# Dispenser.net
KiCad netlist of a schematic drawn in Altium Designer
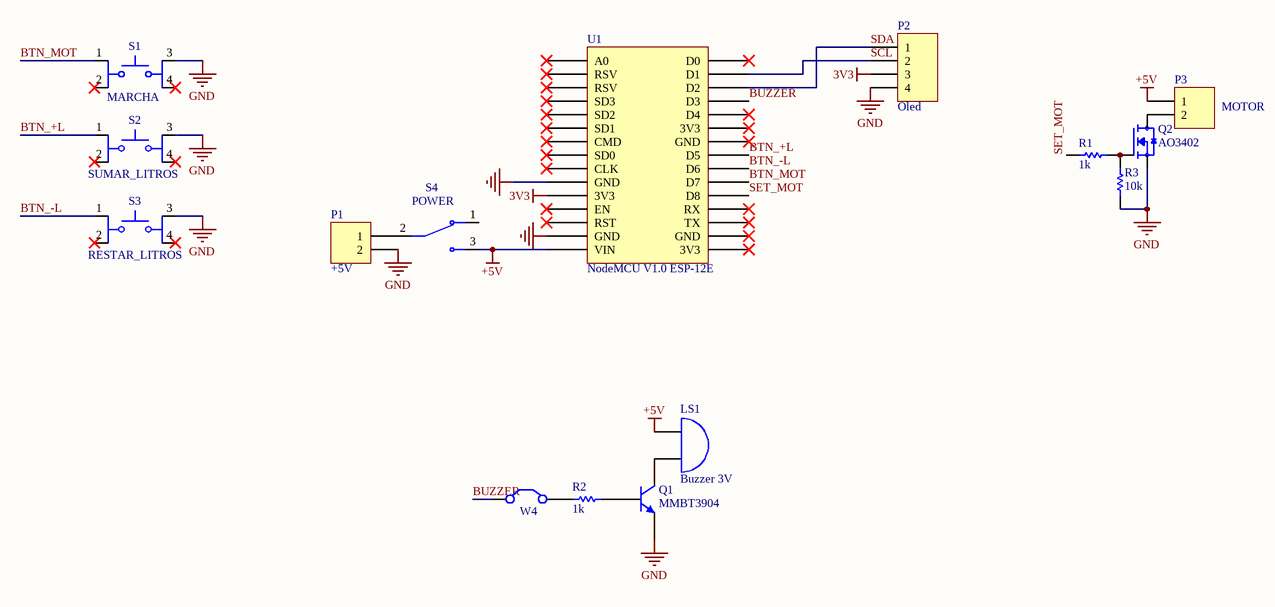
[diagram p0: Dispenser.SchDoc]

(export (version "E")
  (design (tool "Eeschema 10.0.6"))
  (components
    (comp (ref "LS1")
      (value "Buzzer 3V")
      (footprint "BUZZER")
      (description "Electrical Bell")
      (fields (field (name "PUBLISHER") "Altium Limited"))
      (libsource (lib "Miscellaneous Devices") (part "Bell"))
    )
    (comp (ref "P1")
      (value "+5V")
      (footprint "CON1X2")
      (description "Header, 2-Pin")
      (fields (field (name "PUBLISHER") "Altium Limited"))
      (libsource (lib "") (part "Header 2_1"))
    )
    (comp (ref "P2")
      (value "Oled")
      (footprint "HDR1X4")
      (description "Header, 4-Pin")
      (fields (field (name "PUBLISHER") "Altium Limited"))
      (libsource (lib "Miscellaneous Connectors") (part "Header 4"))
    )
    (comp (ref "P3")
      (value "MOTOR")
      (footprint "CON1X2")
      (description "Header, 2-Pin")
      (fields (field (name "PUBLISHER") "Altium Limited"))
      (libsource (lib "Miscellaneous Connectors") (part "Header 2"))
    )
    (comp (ref "Q1")
      (value "MMBT3904")
      (footprint "SOT23_N")
      (description "NPN Switching Transistor")
      (fields (field (name "PUBLISHER") "Altium Limited"))
      (libsource (lib "Philips Discrete BJT - Low Power") (part "MMBT3904"))
    )
    (comp (ref "Q2")
      (value "AO3402")
      (footprint "SOT95P280X125-3N")
      (description "N-Channel 30V 4A _Ta_ 1.4W _Ta_ Surface Mount SOT-23-3L")
      (fields (field (name "MF") "Alpha &") (field (name "DIGI-KEY_PART_NUMBER") "785-1002-1-ND"))
      (libsource (lib "AO3402") (part "AO3402"))
    )
    (comp (ref "R1")
      (value "1k")
      (footprint "RESC2012N")
      (description "Resistor")
      (fields (field (name "PUBLISHER") "Altium Limited"))
      (libsource (lib "Miscellaneous Devices") (part "Res1"))
    )
    (comp (ref "R2")
      (value "1k")
      (footprint "RESC2012N")
      (description "Resistor")
      (fields (field (name "PUBLISHER") "Altium Limited"))
      (libsource (lib "Miscellaneous Devices") (part "Res1"))
    )
    (comp (ref "R3")
      (value "10k")
      (footprint "RESC2012N")
      (description "Resistor")
      (fields (field (name "PUBLISHER") "Altium Limited"))
      (libsource (lib "Miscellaneous Devices") (part "Res1"))
    )
    (comp (ref "S1")
      (value "MARCHA")
      (footprint "SW_TL3301FF160QG")
      (description "SWITCH TACTILE SPST-NO 0.05A 12V")
      (fields (field (name "MF") "E-Switch") (field (name "MP") "TL3301FF160QG"))
      (libsource (lib "PULSADOR") (part "TL3301FF160QG"))
    )
    (comp (ref "S2")
      (value "SUMAR_LITROS")
      (footprint "SW_TL3301FF160QG")
      (description "SWITCH TACTILE SPST-NO 0.05A 12V")
      (fields (field (name "MF") "E-Switch") (field (name "MP") "TL3301FF160QG"))
      (libsource (lib "PULSADOR") (part "TL3301FF160QG"))
    )
    (comp (ref "S3")
      (value "RESTAR_LITROS")
      (footprint "SW_TL3301FF160QG")
      (description "SWITCH TACTILE SPST-NO 0.05A 12V")
      (fields (field (name "MF") "E-Switch") (field (name "MP") "TL3301FF160QG"))
      (libsource (lib "PULSADOR") (part "TL3301FF160QG"))
    )
    (comp (ref "S4")
      (value "POWER")
      (footprint "SW_MINI-SPDT-SW")
      (fields (field (name "MP") "MINI-SPDT-SW"))
      (libsource (lib "MINI-SPDT-SW") (part "MINI-SPDT-SW"))
    )
    (comp (ref "U1")
      (value "NodeMCU V1.0 ESP-12E")
      (footprint "NodeMCU V1.0 ESP-12E")
      (description "NodeMCU V1.0 ESP8266 (ESP-12E)")
      (libsource (lib "nodemcu") (part "NodeMCU V1.0 ESP-12E"))
    )
    (comp (ref "W4")
      (value "Jumper")
      (footprint "RESC1608N")
      (description "Jumper Wire")
      (fields (field (name "PUBLISHER") "Altium Limited"))
      (libsource (lib "Miscellaneous Devices") (part "Jumper"))
    )
  )
  (nets
    (net (code "1") (name "+5V") (class "Default")
      (node (ref "LS1") (pin "1") (pinfunction "A_1") (pintype "passive"))
      (node (ref "P3") (pin "1") (pinfunction "1_1") (pintype "passive"))
      (node (ref "S4") (pin "3") (pinfunction "3_3") (pintype "passive"))
      (node (ref "U1") (pin "VIN") (pinfunction "VIN_VIN") (pintype "passive"))
    )
    (net (code "2") (name "/BTN_+L") (class "Default")
      (node (ref "S2") (pin "1") (pinfunction "1_1") (pintype "passive"))
      (node (ref "U1") (pin "D5") (pinfunction "D5_D5") (pintype "passive"))
    )
    (net (code "3") (name "/BTN_-L") (class "Default")
      (node (ref "S3") (pin "1") (pinfunction "1_1") (pintype "passive"))
      (node (ref "U1") (pin "D6") (pinfunction "D6_D6") (pintype "passive"))
    )
    (net (code "4") (name "/BTN_MOT") (class "Default")
      (node (ref "S1") (pin "1") (pinfunction "1_1") (pintype "passive"))
      (node (ref "U1") (pin "D7") (pinfunction "D7_D7") (pintype "passive"))
    )
    (net (code "5") (name "/BUZZER") (class "Default")
      (node (ref "U1") (pin "D3") (pinfunction "D3_D3") (pintype "passive"))
      (node (ref "W4") (pin "1") (pinfunction "C1_1") (pintype "passive"))
    )
    (net (code "6") (name "/SCL") (class "Default")
      (node (ref "P2") (pin "2") (pinfunction "2_2") (pintype "passive"))
      (node (ref "U1") (pin "D1") (pinfunction "D1_D1") (pintype "passive"))
    )
    (net (code "7") (name "/SDA") (class "Default")
      (node (ref "P2") (pin "1") (pinfunction "1_1") (pintype "passive"))
      (node (ref "U1") (pin "D2") (pinfunction "D2_D2") (pintype "passive"))
    )
    (net (code "8") (name "/SET_MOT") (class "Default")
      (node (ref "R1") (pin "1") (pinfunction "1_1") (pintype "passive"))
      (node (ref "U1") (pin "D8") (pinfunction "D8_D8") (pintype "passive"))
    )
    (net (code "9") (name "3V3") (class "Default")
      (node (ref "P2") (pin "3") (pinfunction "3_3") (pintype "passive"))
      (node (ref "U1") (pin "3V3") (pinfunction "3V3_3V3") (pintype "passive"))
    )
    (net (code "10") (name "GND") (class "Default")
      (node (ref "P1") (pin "2") (pinfunction "2_2") (pintype "passive"))
      (node (ref "P2") (pin "4") (pinfunction "4_4") (pintype "passive"))
      (node (ref "Q1") (pin "2") (pinfunction "E_2") (pintype "passive"))
      (node (ref "Q2") (pin "2") (pinfunction "S_2") (pintype "passive"))
      (node (ref "R3") (pin "1") (pinfunction "1_1") (pintype "passive"))
      (node (ref "S1") (pin "3") (pinfunction "3_3") (pintype "passive"))
      (node (ref "S2") (pin "3") (pinfunction "3_3") (pintype "passive"))
      (node (ref "S3") (pin "3") (pinfunction "3_3") (pintype "passive"))
      (node (ref "U1") (pin "GND") (pinfunction "GND_GND") (pintype "passive"))
    )
    (net (code "11") (name "Net-(LS1-B)") (class "Default")
      (node (ref "LS1") (pin "2") (pinfunction "B_2") (pintype "passive"))
      (node (ref "Q1") (pin "3") (pinfunction "C_3") (pintype "passive"))
    )
    (net (code "12") (name "Net-(P1-Pad1)") (class "Default")
      (node (ref "P1") (pin "1") (pinfunction "1_1") (pintype "passive"))
      (node (ref "S4") (pin "2") (pinfunction "2_2") (pintype "passive"))
    )
    (net (code "13") (name "Net-(Q1-B)") (class "Default")
      (node (ref "Q1") (pin "1") (pinfunction "B_1") (pintype "passive"))
      (node (ref "R2") (pin "2") (pinfunction "2_2") (pintype "passive"))
    )
    (net (code "14") (name "Net-(Q2-D)") (class "Default")
      (node (ref "P3") (pin "2") (pinfunction "2_2") (pintype "passive"))
      (node (ref "Q2") (pin "3") (pinfunction "D_3") (pintype "passive"))
    )
    (net (code "15") (name "Net-(Q2-G)") (class "Default")
      (node (ref "Q2") (pin "1") (pinfunction "G_1") (pintype "passive"))
      (node (ref "R1") (pin "2") (pinfunction "2_2") (pintype "passive"))
      (node (ref "R3") (pin "2") (pinfunction "2_2") (pintype "passive"))
    )
    (net (code "16") (name "Net-(W4-C2)") (class "Default")
      (node (ref "R2") (pin "1") (pinfunction "1_1") (pintype "passive"))
      (node (ref "W4") (pin "2") (pinfunction "C2_2") (pintype "passive"))
    )
    (net (code "17") (name "unconnected-(S1-Pad2)") (class "Default")
      (node (ref "S1") (pin "2") (pinfunction "2_2") (pintype "passive+no_connect"))
    )
    (net (code "18") (name "unconnected-(S1-Pad4)") (class "Default")
      (node (ref "S1") (pin "4") (pinfunction "4_4") (pintype "passive+no_connect"))
    )
    (net (code "19") (name "unconnected-(S2-Pad2)") (class "Default")
      (node (ref "S2") (pin "2") (pinfunction "2_2") (pintype "passive+no_connect"))
    )
    (net (code "20") (name "unconnected-(S2-Pad4)") (class "Default")
      (node (ref "S2") (pin "4") (pinfunction "4_4") (pintype "passive+no_connect"))
    )
    (net (code "21") (name "unconnected-(S3-Pad2)") (class "Default")
      (node (ref "S3") (pin "2") (pinfunction "2_2") (pintype "passive+no_connect"))
    )
    (net (code "22") (name "unconnected-(S3-Pad4)") (class "Default")
      (node (ref "S3") (pin "4") (pinfunction "4_4") (pintype "passive+no_connect"))
    )
    (net (code "23") (name "unconnected-(S4-Pad1)") (class "Default")
      (node (ref "S4") (pin "1") (pinfunction "1_1") (pintype "passive"))
    )
    (net (code "24") (name "unconnected-(U1-Pad3V3)") (class "Default")
      (node (ref "U1") (pin "3V3") (pinfunction "3V3_3V3") (pintype "passive+no_connect"))
    )
    (net (code "25") (name "unconnected-(U1-Pad3V3)_1") (class "Default")
      (node (ref "U1") (pin "3V3") (pinfunction "3V3_3V3") (pintype "passive+no_connect"))
    )
    (net (code "26") (name "unconnected-(U1-PadA0)") (class "Default")
      (node (ref "U1") (pin "A0") (pinfunction "A0_A0") (pintype "passive+no_connect"))
    )
    (net (code "27") (name "unconnected-(U1-PadCLK)") (class "Default")
      (node (ref "U1") (pin "CLK") (pinfunction "CLK_CLK") (pintype "passive+no_connect"))
    )
    (net (code "28") (name "unconnected-(U1-PadCMD)") (class "Default")
      (node (ref "U1") (pin "CMD") (pinfunction "CMD_CMD") (pintype "passive+no_connect"))
    )
    (net (code "29") (name "unconnected-(U1-PadD0)") (class "Default")
      (node (ref "U1") (pin "D0") (pinfunction "D0_D0") (pintype "passive+no_connect"))
    )
    (net (code "30") (name "unconnected-(U1-PadD4)") (class "Default")
      (node (ref "U1") (pin "D4") (pinfunction "D4_D4") (pintype "passive+no_connect"))
    )
    (net (code "31") (name "unconnected-(U1-PadEN)") (class "Default")
      (node (ref "U1") (pin "EN") (pinfunction "EN_EN") (pintype "passive+no_connect"))
    )
    (net (code "32") (name "unconnected-(U1-PadGND)") (class "Default")
      (node (ref "U1") (pin "GND") (pinfunction "GND_GND") (pintype "passive+no_connect"))
    )
    (net (code "33") (name "unconnected-(U1-PadGND)_1") (class "Default")
      (node (ref "U1") (pin "GND") (pinfunction "GND_GND") (pintype "passive+no_connect"))
    )
    (net (code "34") (name "unconnected-(U1-PadRST)") (class "Default")
      (node (ref "U1") (pin "RST") (pinfunction "RST_RST") (pintype "passive+no_connect"))
    )
    (net (code "35") (name "unconnected-(U1-PadRSV)") (class "Default")
      (node (ref "U1") (pin "RSV") (pinfunction "RSV_RSV") (pintype "passive+no_connect"))
    )
    (net (code "36") (name "unconnected-(U1-PadRSV)_1") (class "Default")
      (node (ref "U1") (pin "RSV") (pinfunction "RSV_RSV") (pintype "passive+no_connect"))
    )
    (net (code "37") (name "unconnected-(U1-PadRX)") (class "Default")
      (node (ref "U1") (pin "RX") (pinfunction "RX_RX") (pintype "passive+no_connect"))
    )
    (net (code "38") (name "unconnected-(U1-PadSD0)") (class "Default")
      (node (ref "U1") (pin "SD0") (pinfunction "SD0_SD0") (pintype "passive+no_connect"))
    )
    (net (code "39") (name "unconnected-(U1-PadSD1)") (class "Default")
      (node (ref "U1") (pin "SD1") (pinfunction "SD1_SD1") (pintype "passive+no_connect"))
    )
    (net (code "40") (name "unconnected-(U1-PadSD2)") (class "Default")
      (node (ref "U1") (pin "SD2") (pinfunction "SD2_SD2") (pintype "passive+no_connect"))
    )
    (net (code "41") (name "unconnected-(U1-PadSD3)") (class "Default")
      (node (ref "U1") (pin "SD3") (pinfunction "SD3_SD3") (pintype "passive+no_connect"))
    )
    (net (code "42") (name "unconnected-(U1-PadTX)") (class "Default")
      (node (ref "U1") (pin "TX") (pinfunction "TX_TX") (pintype "passive+no_connect"))
    )
  )
)
